# untitled.net
KiCad netlist of a schematic drawn in EAGLE
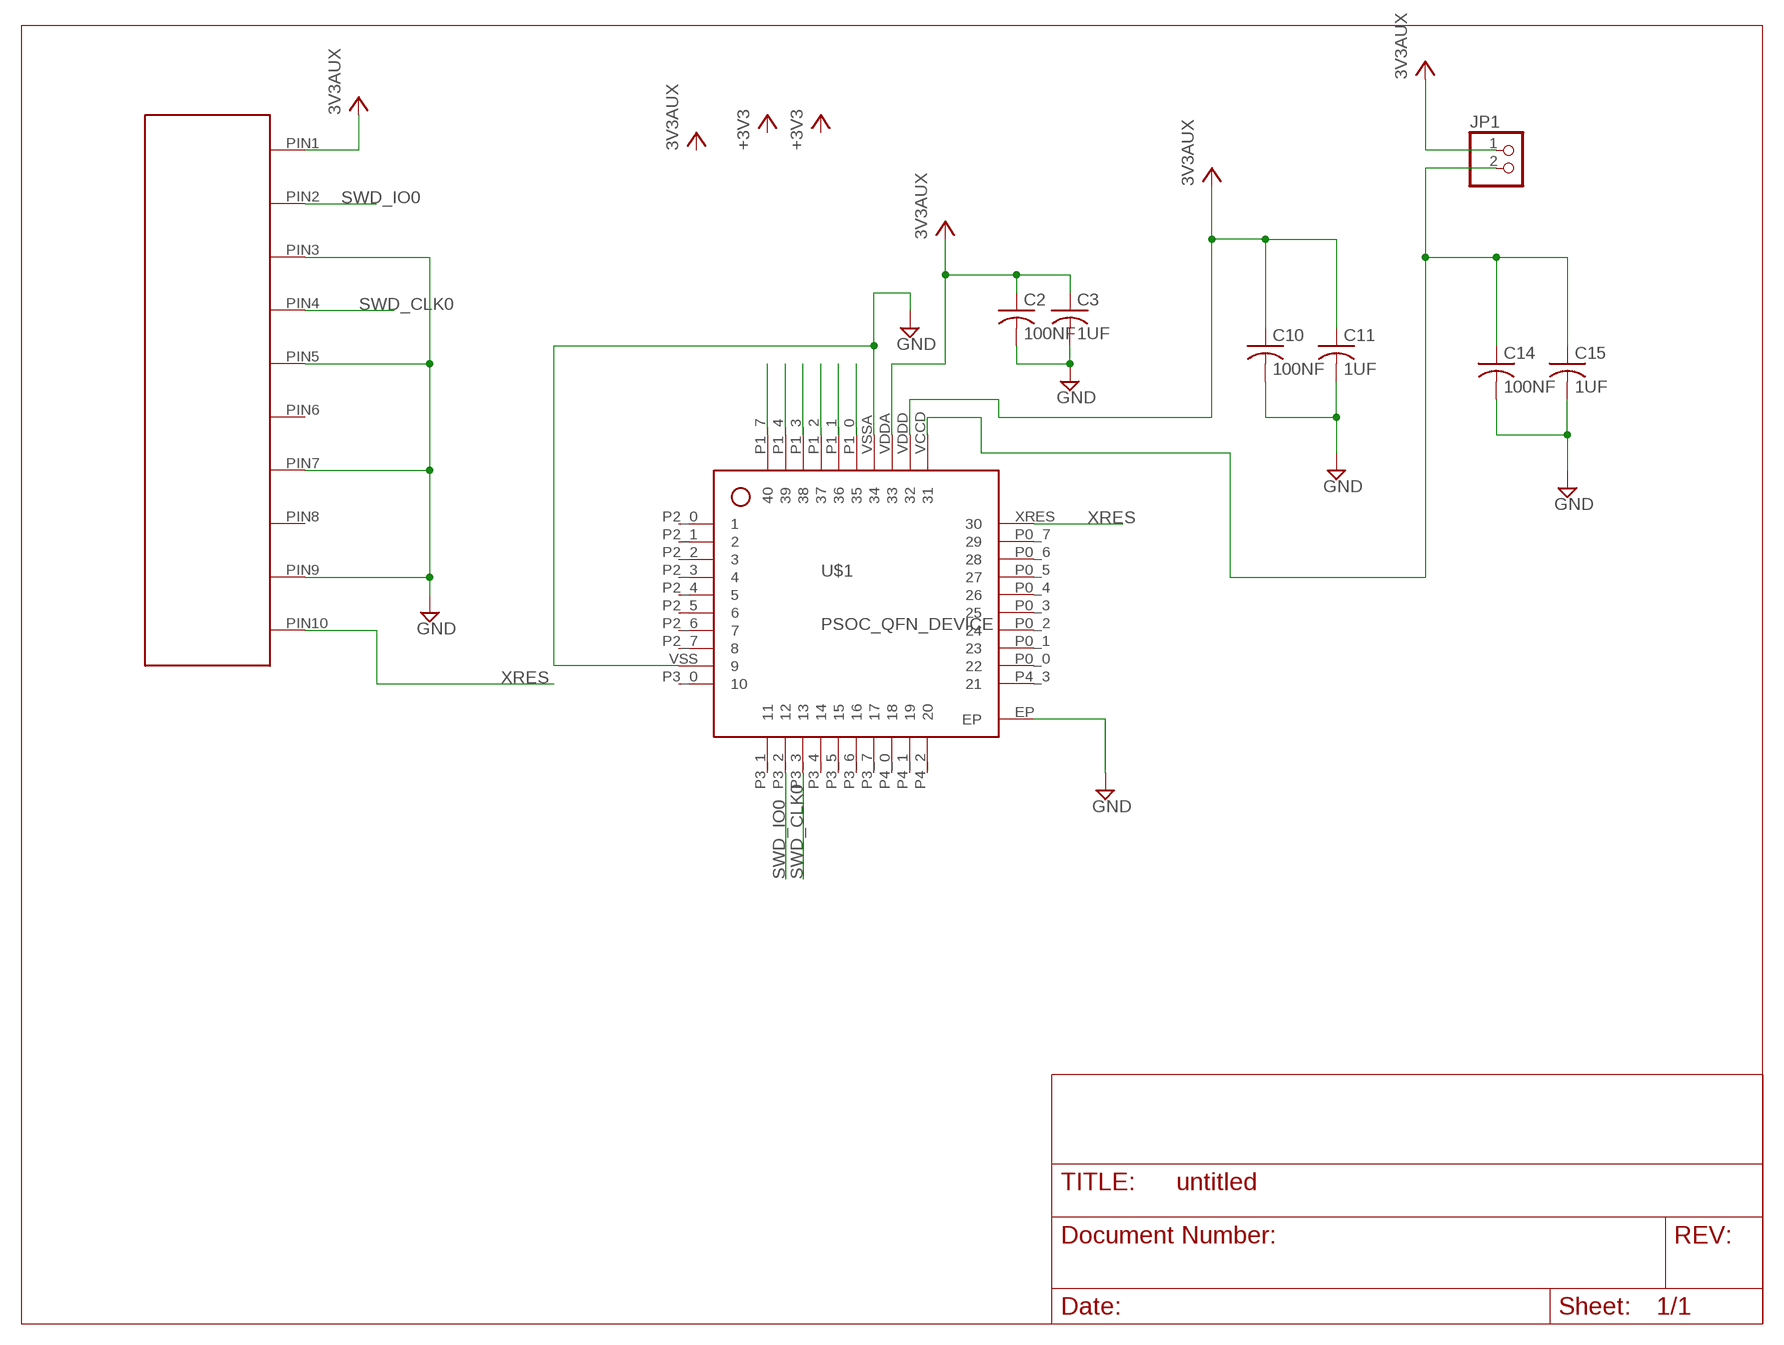
[diagram p0: schematic, sheet 1]

(export (version "E")
  (design (tool "Eeschema 10.0.6"))
  (components
    (comp (ref "C2")
      (value "100NF")
      (footprint "eagle-import:C0603")
      (libsource (lib "eagle-import") (part "C-USC0603"))
    )
    (comp (ref "C3")
      (value "1UF")
      (footprint "eagle-import:C0603")
      (libsource (lib "eagle-import") (part "C-USC0603"))
    )
    (comp (ref "C10")
      (value "100NF")
      (footprint "eagle-import:C0603")
      (libsource (lib "eagle-import") (part "C-USC0603"))
    )
    (comp (ref "C11")
      (value "1UF")
      (footprint "eagle-import:C0603")
      (libsource (lib "eagle-import") (part "C-USC0603"))
    )
    (comp (ref "C14")
      (value "100NF")
      (footprint "eagle-import:C0603")
      (libsource (lib "eagle-import") (part "C-USC0603"))
    )
    (comp (ref "C15")
      (value "1UF")
      (footprint "eagle-import:C0603")
      (libsource (lib "eagle-import") (part "C-USC0603"))
    )
    (comp (ref "JP1")
      (value "PINHD-1X2")
      (footprint "eagle-import:1X02")
      (libsource (lib "eagle-import") (part "PINHD-1X2"))
    )
    (comp (ref "U$1")
      (value "PSOC_QFN_DEVICE")
      (footprint "eagle-import:PSOC_QFN_PACKEGE")
      (libsource (lib "eagle-import") (part "PSOC_QFN_DEVICE"))
    )
    (comp (ref "U$2")
      (value "PSOC_10_PIN_HEADER_DEVICE")
      (footprint "eagle-import:PSOC_10_PIN_HEADER")
      (libsource (lib "eagle-import") (part "PSOC_10_PIN_HEADER_DEVICE"))
    )
  )
  (nets
    (net (code "2") (name "/SWD_CLK0") (class "Default")
      (node (ref "U$1") (pin "P3_3") (pinfunction "13_P3_3") (pintype "bidirectional"))
      (node (ref "U$2") (pin "PIN4") (pinfunction "SWD_CLK0_PIN4") (pintype "bidirectional"))
    )
    (net (code "3") (name "/SWD_IO0") (class "Default")
      (node (ref "U$1") (pin "P3_2") (pinfunction "12_P3_2") (pintype "bidirectional"))
      (node (ref "U$2") (pin "PIN2") (pinfunction "SWD_IO0_PIN2") (pintype "bidirectional"))
    )
    (net (code "4") (name "/XRES") (class "Default")
      (node (ref "U$1") (pin "XRES") (pinfunction "30_XRES") (pintype "bidirectional"))
      (node (ref "U$2") (pin "PIN10") (pinfunction "XRES_PIN10") (pintype "bidirectional"))
    )
    (net (code "5") (name "3V3AUX") (class "Default")
      (node (ref "C10") (pin "1") (pinfunction "1_1") (pintype "passive"))
      (node (ref "C11") (pin "1") (pinfunction "1_1") (pintype "passive"))
      (node (ref "C2") (pin "1") (pinfunction "1_1") (pintype "passive"))
      (node (ref "C3") (pin "1") (pinfunction "1_1") (pintype "passive"))
      (node (ref "JP1") (pin "1") (pinfunction "1_1") (pintype "passive"))
      (node (ref "U$1") (pin "VDDA") (pinfunction "33_VDDA") (pintype "bidirectional"))
      (node (ref "U$1") (pin "VDDD") (pinfunction "32_VDDD") (pintype "bidirectional"))
      (node (ref "U$2") (pin "PIN1") (pinfunction "3V3_AUX_PIN1") (pintype "bidirectional"))
    )
    (net (code "6") (name "GND") (class "Default")
      (node (ref "C10") (pin "2") (pinfunction "2_2") (pintype "passive"))
      (node (ref "C11") (pin "2") (pinfunction "2_2") (pintype "passive"))
      (node (ref "C14") (pin "2") (pinfunction "2_2") (pintype "passive"))
      (node (ref "C15") (pin "2") (pinfunction "2_2") (pintype "passive"))
      (node (ref "C2") (pin "2") (pinfunction "2_2") (pintype "passive"))
      (node (ref "C3") (pin "2") (pinfunction "2_2") (pintype "passive"))
      (node (ref "U$1") (pin "EP") (pinfunction "EP_EP") (pintype "bidirectional"))
      (node (ref "U$1") (pin "VSS") (pinfunction "9_VSS") (pintype "bidirectional"))
      (node (ref "U$1") (pin "VSSA") (pinfunction "34_VSSA") (pintype "bidirectional"))
      (node (ref "U$2") (pin "PIN3") (pinfunction "GND_PIN3") (pintype "bidirectional"))
      (node (ref "U$2") (pin "PIN5") (pinfunction "GND_PIN5") (pintype "bidirectional"))
      (node (ref "U$2") (pin "PIN7") (pinfunction "GND_PIN7") (pintype "bidirectional"))
      (node (ref "U$2") (pin "PIN9") (pinfunction "GND_PIN9") (pintype "bidirectional"))
    )
    (net (code "7") (name "Net-(U$1-31)") (class "Default")
      (node (ref "C14") (pin "1") (pinfunction "1_1") (pintype "passive"))
      (node (ref "C15") (pin "1") (pinfunction "1_1") (pintype "passive"))
      (node (ref "JP1") (pin "2") (pinfunction "2_2") (pintype "passive"))
      (node (ref "U$1") (pin "VCCD") (pinfunction "31_VCCD") (pintype "bidirectional"))
    )
    (net (code "8") (name "unconnected-(U$1-1-PadP2_0)") (class "Default")
      (node (ref "U$1") (pin "P2_0") (pinfunction "1_P2_0") (pintype "bidirectional"))
    )
    (net (code "9") (name "unconnected-(U$1-2-PadP2_1)") (class "Default")
      (node (ref "U$1") (pin "P2_1") (pinfunction "2_P2_1") (pintype "bidirectional"))
    )
    (net (code "10") (name "unconnected-(U$1-3-PadP2_2)") (class "Default")
      (node (ref "U$1") (pin "P2_2") (pinfunction "3_P2_2") (pintype "bidirectional"))
    )
    (net (code "11") (name "unconnected-(U$1-4-PadP2_3)") (class "Default")
      (node (ref "U$1") (pin "P2_3") (pinfunction "4_P2_3") (pintype "bidirectional"))
    )
    (net (code "12") (name "unconnected-(U$1-5-PadP2_4)") (class "Default")
      (node (ref "U$1") (pin "P2_4") (pinfunction "5_P2_4") (pintype "bidirectional"))
    )
    (net (code "13") (name "unconnected-(U$1-6-PadP2_5)") (class "Default")
      (node (ref "U$1") (pin "P2_5") (pinfunction "6_P2_5") (pintype "bidirectional"))
    )
    (net (code "14") (name "unconnected-(U$1-7-PadP2_6)") (class "Default")
      (node (ref "U$1") (pin "P2_6") (pinfunction "7_P2_6") (pintype "bidirectional"))
    )
    (net (code "15") (name "unconnected-(U$1-8-PadP2_7)") (class "Default")
      (node (ref "U$1") (pin "P2_7") (pinfunction "8_P2_7") (pintype "bidirectional"))
    )
    (net (code "16") (name "unconnected-(U$1-10-PadP3_0)") (class "Default")
      (node (ref "U$1") (pin "P3_0") (pinfunction "10_P3_0") (pintype "bidirectional"))
    )
    (net (code "17") (name "unconnected-(U$1-11-PadP3_1)") (class "Default")
      (node (ref "U$1") (pin "P3_1") (pinfunction "11_P3_1") (pintype "bidirectional"))
    )
    (net (code "18") (name "unconnected-(U$1-14-PadP3_4)") (class "Default")
      (node (ref "U$1") (pin "P3_4") (pinfunction "14_P3_4") (pintype "bidirectional"))
    )
    (net (code "19") (name "unconnected-(U$1-15-PadP3_5)") (class "Default")
      (node (ref "U$1") (pin "P3_5") (pinfunction "15_P3_5") (pintype "bidirectional"))
    )
    (net (code "20") (name "unconnected-(U$1-16-PadP3_6)") (class "Default")
      (node (ref "U$1") (pin "P3_6") (pinfunction "16_P3_6") (pintype "bidirectional"))
    )
    (net (code "21") (name "unconnected-(U$1-17-PadP3_7)") (class "Default")
      (node (ref "U$1") (pin "P3_7") (pinfunction "17_P3_7") (pintype "bidirectional"))
    )
    (net (code "22") (name "unconnected-(U$1-18-PadP4_0)") (class "Default")
      (node (ref "U$1") (pin "P4_0") (pinfunction "18_P4_0") (pintype "bidirectional"))
    )
    (net (code "23") (name "unconnected-(U$1-19-PadP4_1)") (class "Default")
      (node (ref "U$1") (pin "P4_1") (pinfunction "19_P4_1") (pintype "bidirectional"))
    )
    (net (code "24") (name "unconnected-(U$1-20-PadP4_2)") (class "Default")
      (node (ref "U$1") (pin "P4_2") (pinfunction "20_P4_2") (pintype "bidirectional"))
    )
    (net (code "25") (name "unconnected-(U$1-21-PadP4_3)") (class "Default")
      (node (ref "U$1") (pin "P4_3") (pinfunction "21_P4_3") (pintype "bidirectional"))
    )
    (net (code "26") (name "unconnected-(U$1-22-PadP0_0)") (class "Default")
      (node (ref "U$1") (pin "P0_0") (pinfunction "22_P0_0") (pintype "bidirectional"))
    )
    (net (code "27") (name "unconnected-(U$1-23-PadP0_1)") (class "Default")
      (node (ref "U$1") (pin "P0_1") (pinfunction "23_P0_1") (pintype "bidirectional"))
    )
    (net (code "28") (name "unconnected-(U$1-24-PadP0_2)") (class "Default")
      (node (ref "U$1") (pin "P0_2") (pinfunction "24_P0_2") (pintype "bidirectional"))
    )
    (net (code "29") (name "unconnected-(U$1-25-PadP0_3)") (class "Default")
      (node (ref "U$1") (pin "P0_3") (pinfunction "25_P0_3") (pintype "bidirectional"))
    )
    (net (code "30") (name "unconnected-(U$1-26-PadP0_4)") (class "Default")
      (node (ref "U$1") (pin "P0_4") (pinfunction "26_P0_4") (pintype "bidirectional"))
    )
    (net (code "31") (name "unconnected-(U$1-27-PadP0_5)") (class "Default")
      (node (ref "U$1") (pin "P0_5") (pinfunction "27_P0_5") (pintype "bidirectional"))
    )
    (net (code "32") (name "unconnected-(U$1-28-PadP0_6)") (class "Default")
      (node (ref "U$1") (pin "P0_6") (pinfunction "28_P0_6") (pintype "bidirectional"))
    )
    (net (code "33") (name "unconnected-(U$1-29-PadP0_7)") (class "Default")
      (node (ref "U$1") (pin "P0_7") (pinfunction "29_P0_7") (pintype "bidirectional"))
    )
    (net (code "34") (name "unconnected-(U$1-35-PadP1_0)") (class "Default")
      (node (ref "U$1") (pin "P1_0") (pinfunction "35_P1_0") (pintype "bidirectional"))
    )
    (net (code "35") (name "unconnected-(U$1-36-PadP1_1)") (class "Default")
      (node (ref "U$1") (pin "P1_1") (pinfunction "36_P1_1") (pintype "bidirectional"))
    )
    (net (code "36") (name "unconnected-(U$1-37-PadP1_2)") (class "Default")
      (node (ref "U$1") (pin "P1_2") (pinfunction "37_P1_2") (pintype "bidirectional"))
    )
    (net (code "37") (name "unconnected-(U$1-38-PadP1_3)") (class "Default")
      (node (ref "U$1") (pin "P1_3") (pinfunction "38_P1_3") (pintype "bidirectional"))
    )
    (net (code "38") (name "unconnected-(U$1-39-PadP1_4)") (class "Default")
      (node (ref "U$1") (pin "P1_4") (pinfunction "39_P1_4") (pintype "bidirectional"))
    )
    (net (code "39") (name "unconnected-(U$1-40-PadP1_7)") (class "Default")
      (node (ref "U$1") (pin "P1_7") (pinfunction "40_P1_7") (pintype "bidirectional"))
    )
    (net (code "40") (name "unconnected-(U$2-NC-PadPIN6)") (class "Default")
      (node (ref "U$2") (pin "PIN6") (pinfunction "NC_PIN6") (pintype "bidirectional"))
    )
    (net (code "41") (name "unconnected-(U$2-NC2-PadPIN8)") (class "Default")
      (node (ref "U$2") (pin "PIN8") (pinfunction "NC2_PIN8") (pintype "bidirectional"))
    )
  )
)
